# Outlet_Sensor.net
KiCad netlist of a schematic drawn in EAGLE
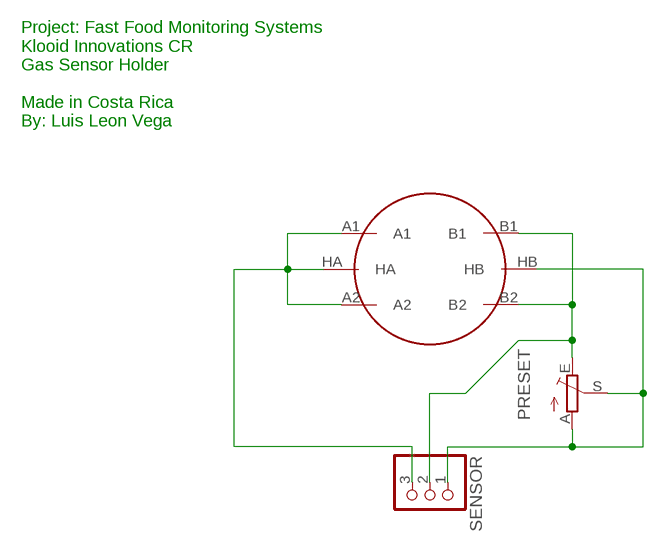
[diagram p0: schematic, sheet 1]

(export (version "E")
  (design (tool "Eeschema 10.0.6"))
  (components
    (comp (ref "PRESET")
      (value "TRIM_EU-B25P")
      (footprint "eagle-import:B25P")
      (libsource (lib "eagle-import") (part "TRIM_EU-B25P"))
    )
    (comp (ref "SENSOR")
      (value "PINHD-1X3")
      (footprint "eagle-import:1X03")
      (libsource (lib "eagle-import") (part "PINHD-1X3"))
    )
    (comp (ref "U$1")
      (value "METHANE_SENSOR")
      (footprint "eagle-import:MQ-3")
      (libsource (lib "eagle-import") (part "METHANE_SENSOR"))
    )
  )
  (nets
    (net (code "1") (name "Net-(PRESET-PadA)") (class "Default")
      (node (ref "PRESET") (pin "A") (pinfunction "A_A") (pintype "passive"))
      (node (ref "PRESET") (pin "S") (pinfunction "S_S") (pintype "passive"))
      (node (ref "SENSOR") (pin "1") (pinfunction "1_1") (pintype "passive"))
      (node (ref "U$1") (pin "HB") (pinfunction "HB_HB") (pintype "bidirectional"))
    )
    (net (code "2") (name "Net-(PRESET-PadE)") (class "Default")
      (node (ref "PRESET") (pin "E") (pinfunction "E_E") (pintype "passive"))
      (node (ref "SENSOR") (pin "2") (pinfunction "2_2") (pintype "passive"))
      (node (ref "U$1") (pin "B1") (pinfunction "B1_B1") (pintype "bidirectional"))
      (node (ref "U$1") (pin "B2") (pinfunction "B2_B2") (pintype "bidirectional"))
    )
    (net (code "3") (name "Net-(SENSOR-Pad3)") (class "Default")
      (node (ref "SENSOR") (pin "3") (pinfunction "3_3") (pintype "passive"))
      (node (ref "U$1") (pin "A1") (pinfunction "A1_A1") (pintype "bidirectional"))
      (node (ref "U$1") (pin "A2") (pinfunction "A2_A2") (pintype "bidirectional"))
      (node (ref "U$1") (pin "HA") (pinfunction "HA_HA") (pintype "bidirectional"))
    )
  )
)
